# PhotoDiodeMiniBoard.net
KiCad netlist of a schematic drawn in EAGLE
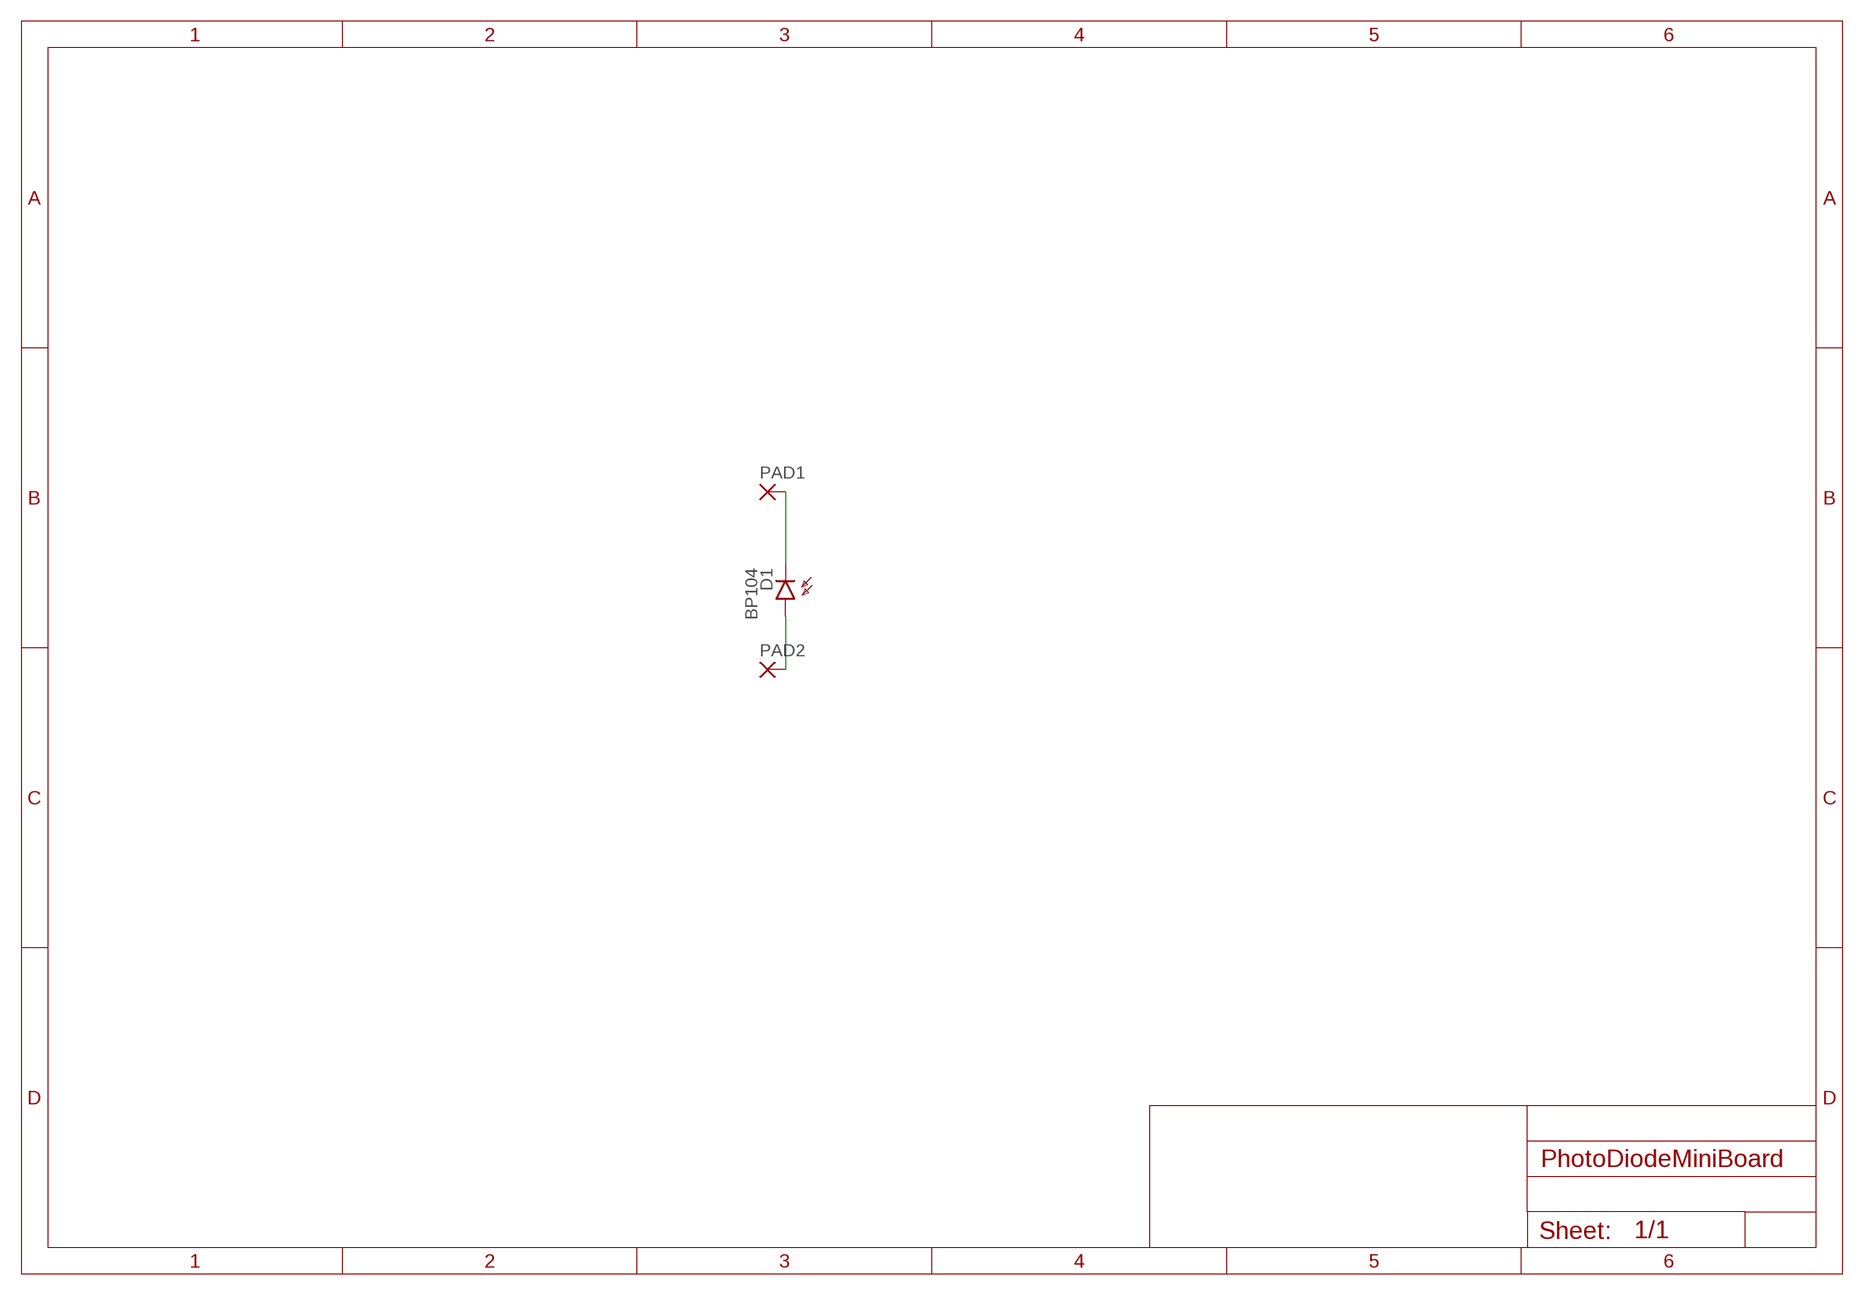
[diagram p0: schematic, sheet 1]

(export (version "E")
  (design (tool "Eeschema 10.0.6"))
  (components
    (comp (ref "D1")
      (value "BP104")
      (footprint "eagle-import:BP104")
      (fields (field (name "MF") "VISHAY/TELEFUNKEN"))
      (libsource (lib "eagle-import") (part "BP104"))
    )
    (comp (ref "PAD1")
      (value "2,15/1,0")
      (footprint "eagle-import:2,15_1,0")
      (libsource (lib "eagle-import") (part "2,15/1,0"))
    )
    (comp (ref "PAD2")
      (value "2,15/1,0")
      (footprint "eagle-import:2,15_1,0")
      (libsource (lib "eagle-import") (part "2,15/1,0"))
    )
  )
  (nets
    (net (code "1") (name "Net-(D1-C)") (class "Default")
      (node (ref "D1") (pin "K") (pinfunction "C_K") (pintype "passive"))
      (node (ref "PAD1") (pin "1") (pinfunction "P_1") (pintype "passive"))
    )
    (net (code "2") (name "Net-(PAD2-P)") (class "Default")
      (node (ref "D1") (pin "A") (pinfunction "A_A") (pintype "passive"))
      (node (ref "PAD2") (pin "1") (pinfunction "P_1") (pintype "passive"))
    )
  )
)
